# pwrboard.net
KiCad netlist of a schematic drawn in EAGLE
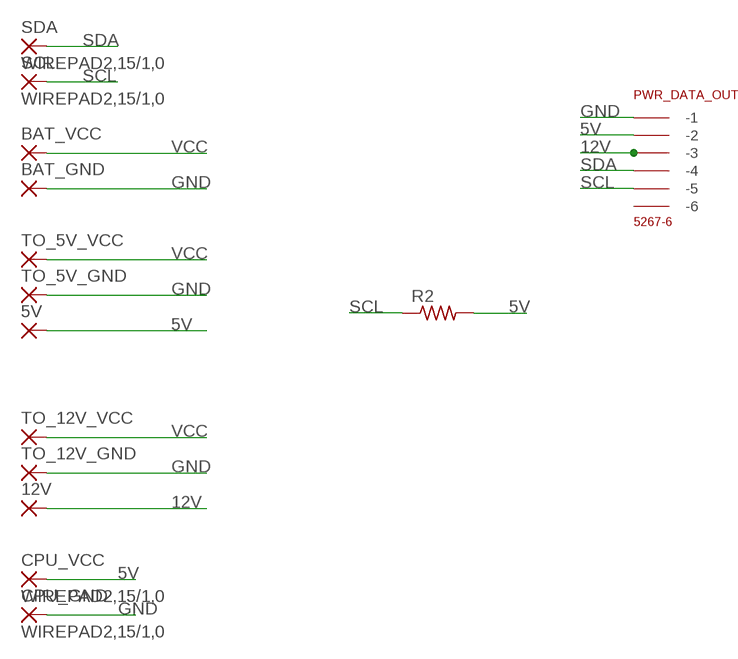
[diagram p0: schematic, sheet 1]

(export (version "E")
  (design (tool "Eeschema 10.0.6"))
  (components
    (comp (ref "5V")
      (value "SMD5")
      (footprint "eagle-import:SMD2,54-5,08")
      (libsource (lib "eagle-import") (part "SMD5"))
    )
    (comp (ref "12V")
      (value "SMD5")
      (footprint "eagle-import:SMD2,54-5,08")
      (libsource (lib "eagle-import") (part "SMD5"))
    )
    (comp (ref "BAT_GND")
      (value "SMD5")
      (footprint "eagle-import:SMD2,54-5,08")
      (libsource (lib "eagle-import") (part "SMD5"))
    )
    (comp (ref "BAT_VCC")
      (value "SMD5")
      (footprint "eagle-import:SMD2,54-5,08")
      (libsource (lib "eagle-import") (part "SMD5"))
    )
    (comp (ref "CPU_GND")
      (value "WIREPAD2,15/1,0")
      (footprint "eagle-import:2,15_1,0")
      (libsource (lib "eagle-import") (part "WIREPAD2,15/1,0"))
    )
    (comp (ref "CPU_VCC")
      (value "WIREPAD2,15/1,0")
      (footprint "eagle-import:2,15_1,0")
      (libsource (lib "eagle-import") (part "WIREPAD2,15/1,0"))
    )
    (comp (ref "PWR_DATA_OUT")
      (value "5267-6")
      (footprint "eagle-import:5267-6")
      (libsource (lib "eagle-import") (part "5267-6"))
    )
    (comp (ref "R2")
      (value "R-US_R1210")
      (footprint "eagle-import:R1210")
      (libsource (lib "eagle-import") (part "R-US_R1210"))
    )
    (comp (ref "SCL")
      (value "WIREPAD2,15/1,0")
      (footprint "eagle-import:2,15_1,0")
      (libsource (lib "eagle-import") (part "WIREPAD2,15/1,0"))
    )
    (comp (ref "SDA")
      (value "WIREPAD2,15/1,0")
      (footprint "eagle-import:2,15_1,0")
      (libsource (lib "eagle-import") (part "WIREPAD2,15/1,0"))
    )
    (comp (ref "TO_5V_GND")
      (value "SMD5")
      (footprint "eagle-import:SMD2,54-5,08")
      (libsource (lib "eagle-import") (part "SMD5"))
    )
    (comp (ref "TO_5V_VCC")
      (value "SMD5")
      (footprint "eagle-import:SMD2,54-5,08")
      (libsource (lib "eagle-import") (part "SMD5"))
    )
    (comp (ref "TO_12V_GND")
      (value "SMD5")
      (footprint "eagle-import:SMD2,54-5,08")
      (libsource (lib "eagle-import") (part "SMD5"))
    )
    (comp (ref "TO_12V_VCC")
      (value "SMD5")
      (footprint "eagle-import:SMD2,54-5,08")
      (libsource (lib "eagle-import") (part "SMD5"))
    )
  )
  (nets
    (net (code "1") (name "/5V") (class "Default")
      (node (ref "5V") (pin "1") (pinfunction "P_1") (pintype "passive"))
      (node (ref "CPU_VCC") (pin "1") (pinfunction "P_1") (pintype "passive"))
      (node (ref "PWR_DATA_OUT") (pin "P$2") (pinfunction "-2_P$2") (pintype "bidirectional"))
      (node (ref "R2") (pin "2") (pinfunction "2_2") (pintype "passive"))
    )
    (net (code "2") (name "/12V") (class "Default")
      (node (ref "12V") (pin "1") (pinfunction "P_1") (pintype "passive"))
      (node (ref "PWR_DATA_OUT") (pin "P$3") (pinfunction "-3_P$3") (pintype "bidirectional"))
    )
    (net (code "3") (name "/GND") (class "Default")
      (node (ref "BAT_GND") (pin "1") (pinfunction "P_1") (pintype "passive"))
      (node (ref "CPU_GND") (pin "1") (pinfunction "P_1") (pintype "passive"))
      (node (ref "PWR_DATA_OUT") (pin "P$1") (pinfunction "-1_P$1") (pintype "bidirectional"))
      (node (ref "TO_12V_GND") (pin "1") (pinfunction "P_1") (pintype "passive"))
      (node (ref "TO_5V_GND") (pin "1") (pinfunction "P_1") (pintype "passive"))
    )
    (net (code "4") (name "/SCL") (class "Default")
      (node (ref "PWR_DATA_OUT") (pin "P$5") (pinfunction "-5_P$5") (pintype "bidirectional"))
      (node (ref "R2") (pin "1") (pinfunction "1_1") (pintype "passive"))
      (node (ref "SCL") (pin "1") (pinfunction "P_1") (pintype "passive"))
    )
    (net (code "5") (name "/SDA") (class "Default")
      (node (ref "PWR_DATA_OUT") (pin "P$4") (pinfunction "-4_P$4") (pintype "bidirectional"))
      (node (ref "SDA") (pin "1") (pinfunction "P_1") (pintype "passive"))
    )
    (net (code "6") (name "/VCC") (class "Default")
      (node (ref "BAT_VCC") (pin "1") (pinfunction "P_1") (pintype "passive"))
      (node (ref "TO_12V_VCC") (pin "1") (pinfunction "P_1") (pintype "passive"))
      (node (ref "TO_5V_VCC") (pin "1") (pinfunction "P_1") (pintype "passive"))
    )
    (net (code "7") (name "unconnected-(PWR_DATA_OUT--6-PadP$6)") (class "Default")
      (node (ref "PWR_DATA_OUT") (pin "P$6") (pinfunction "-6_P$6") (pintype "bidirectional"))
    )
  )
)
